# design.net
KiCad netlist of a schematic drawn in Altium Designer
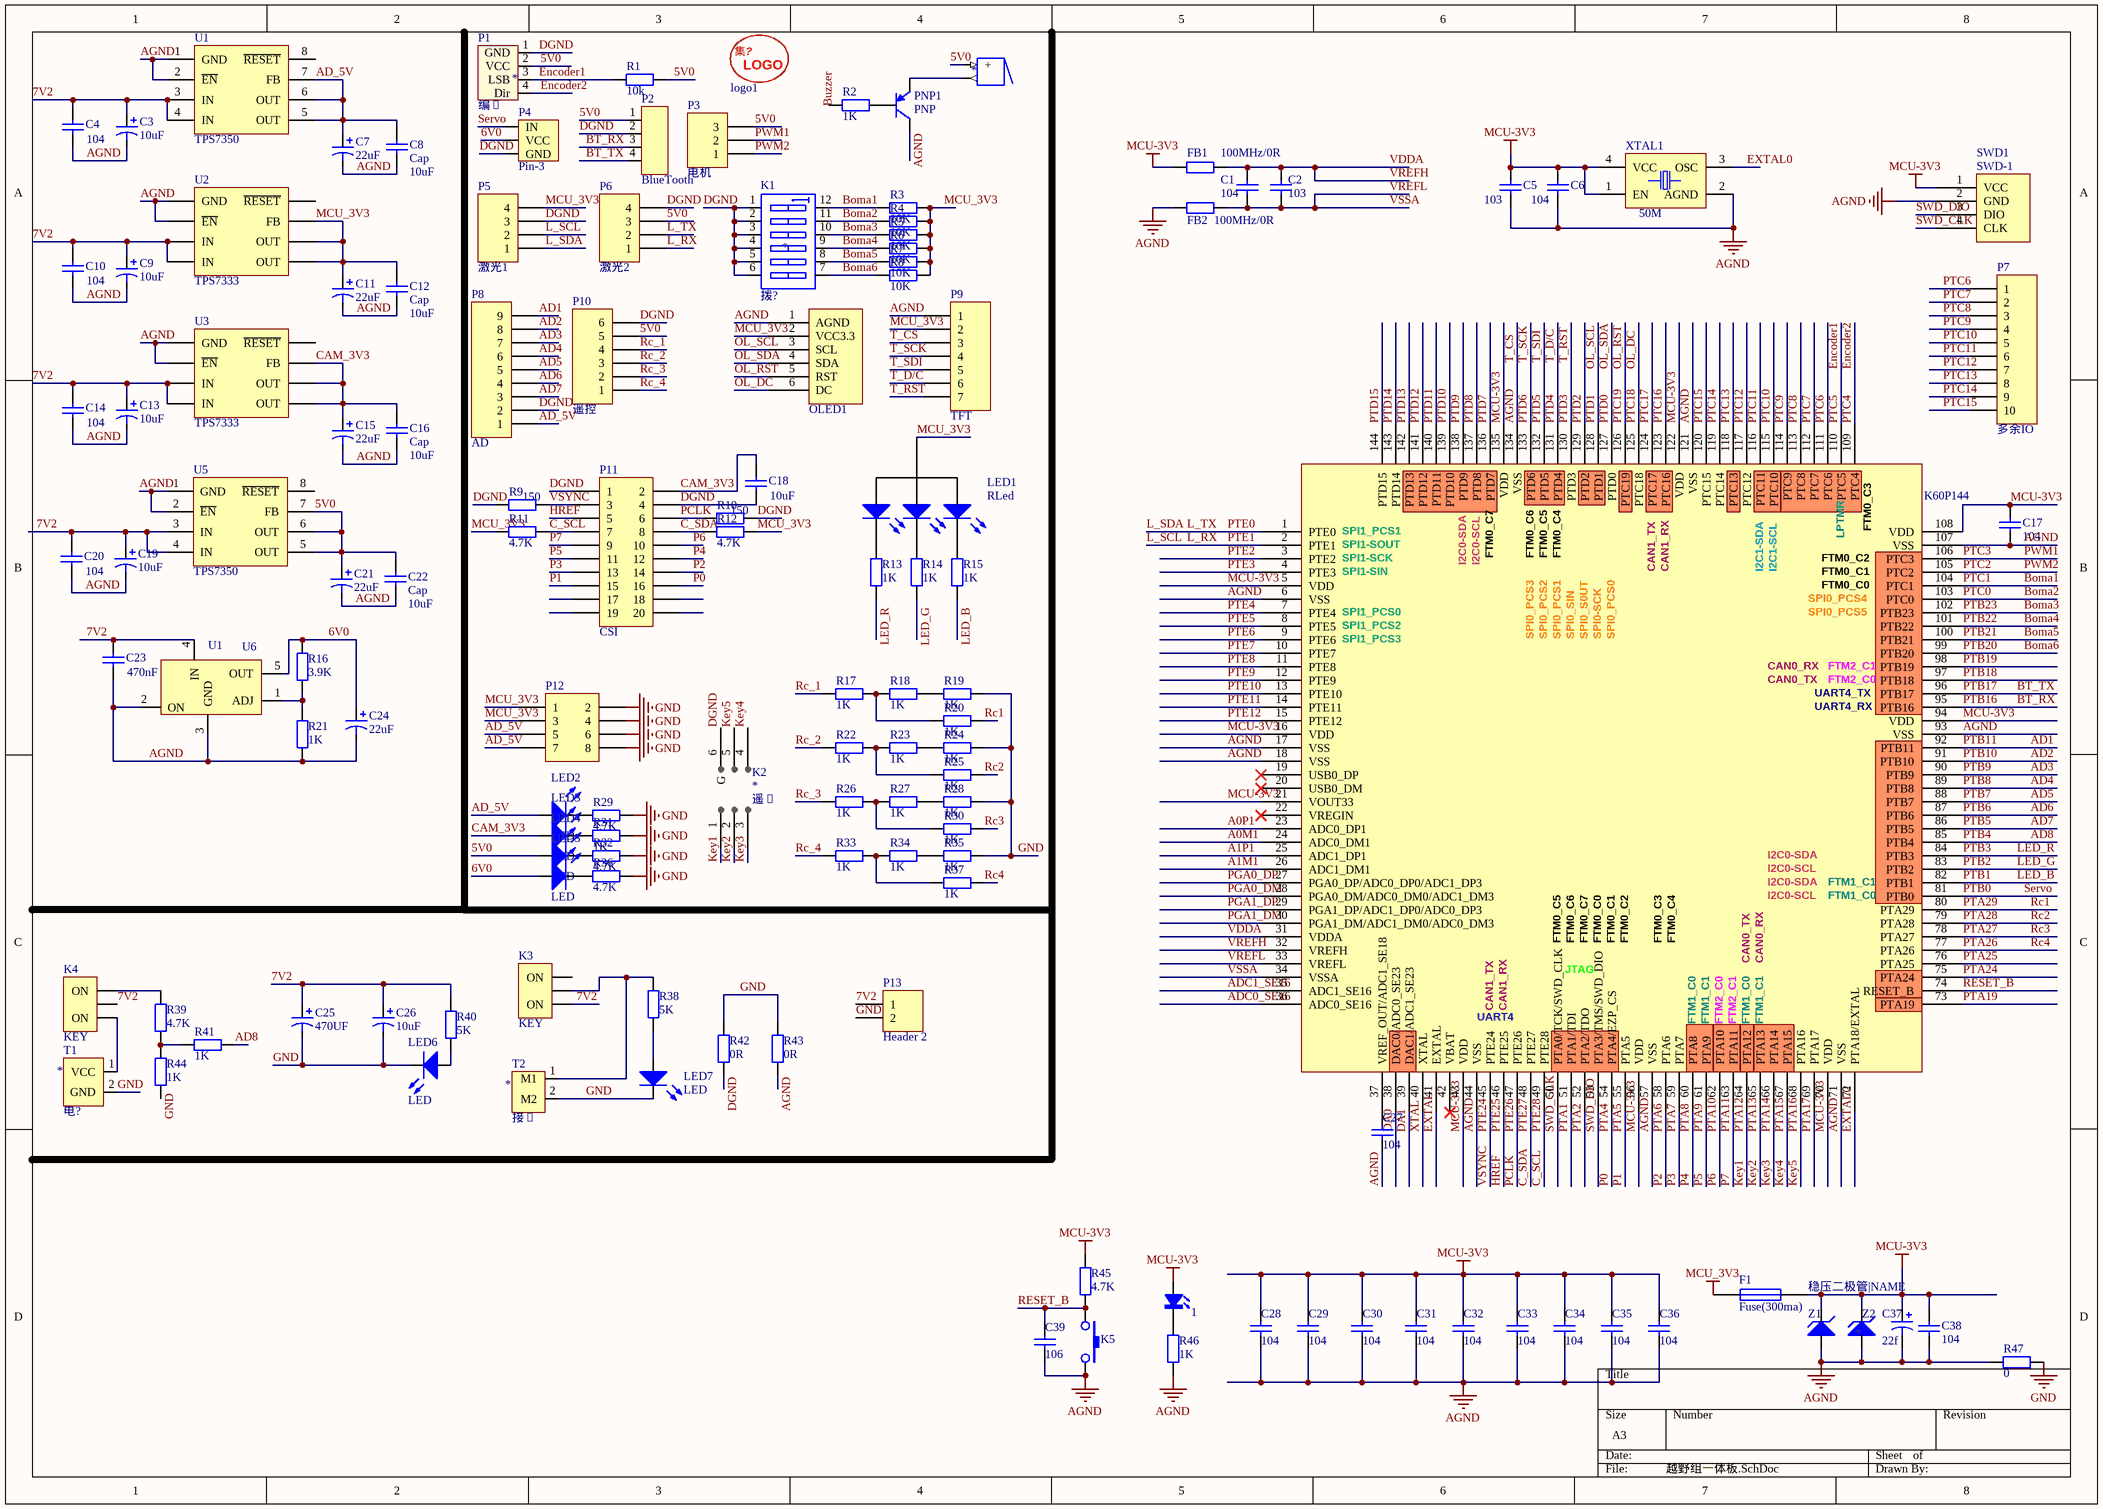
[diagram p0: 越野组一体板.SchDoc]

(export (version "E")
  (design (tool "Eeschema 10.0.6"))
  (components
    (comp (ref "1") (value "LED") (footprint "0805LED1") (libsource (lib "Bigbear") (part "LED")))
    (comp (ref "BUZZER1")
      (value "*")
      (footprint "Buzzer")
      (libsource (lib "JMU智能车专用2.0.6") (part "Buzzer(有源蜂鸣器)"))
    )
    (comp (ref "C1") (value "104") (footprint "0805-0C") (libsource (lib "K60P144") (part "CAP")))
    (comp (ref "C2") (value "103") (footprint "0805-0C") (libsource (lib "K60P144") (part "CAP")))
    (comp (ref "C3")
      (value "10uF")
      (footprint "pol cap(10uF)")
      (description "通用有极电容")
      (fields (field (name "Comment") "pol cap"))
      (libsource (lib "JMU智能车专用2.0.6") (part "pol cap"))
    )
    (comp (ref "C4")
      (value "104")
      (footprint "0805")
      (description "无极电容")
      (libsource (lib "JMU智能车专用2.0.6") (part "Cap"))
    )
    (comp (ref "C5") (value "103") (footprint "0805-0C") (libsource (lib "Bigbear") (part "CAP")))
    (comp (ref "C6") (value "104") (footprint "0805-0C") (libsource (lib "Bigbear") (part "CAP")))
    (comp (ref "C7")
      (value "22uF")
      (footprint "pol cap(10uF)")
      (description "通用有极电容")
      (fields (field (name "Comment") "pol cap"))
      (libsource (lib "JMU智能车专用2.0.6") (part "pol cap"))
    )
    (comp (ref "C8")
      (value "Cap")
      (footprint "0805")
      (description "无极电容")
      (fields (field (name "ALTIUM_VALUE") "10uF"))
      (libsource (lib "JMU智能车专用2.0.6") (part "Cap"))
    )
    (comp (ref "C9")
      (value "10uF")
      (footprint "pol cap(10uF)")
      (description "通用有极电容")
      (fields (field (name "Comment") "pol cap"))
      (libsource (lib "JMU智能车专用2.0.6") (part "pol cap"))
    )
    (comp (ref "C10")
      (value "104")
      (footprint "0805")
      (description "无极电容")
      (libsource (lib "JMU智能车专用2.0.6") (part "Cap"))
    )
    (comp (ref "C11")
      (value "22uF")
      (footprint "pol cap(10uF)")
      (description "通用有极电容")
      (fields (field (name "Comment") "pol cap"))
      (libsource (lib "JMU智能车专用2.0.6") (part "pol cap"))
    )
    (comp (ref "C12")
      (value "Cap")
      (footprint "0805")
      (description "无极电容")
      (fields (field (name "ALTIUM_VALUE") "10uF"))
      (libsource (lib "JMU智能车专用2.0.6") (part "Cap"))
    )
    (comp (ref "C13")
      (value "10uF")
      (footprint "pol cap(10uF)")
      (description "通用有极电容")
      (fields (field (name "Comment") "pol cap"))
      (libsource (lib "JMU智能车专用2.0.6") (part "pol cap"))
    )
    (comp (ref "C14")
      (value "104")
      (footprint "0805")
      (description "无极电容")
      (libsource (lib "JMU智能车专用2.0.6") (part "Cap"))
    )
    (comp (ref "C15")
      (value "22uF")
      (footprint "pol cap(10uF)")
      (description "通用有极电容")
      (fields (field (name "Comment") "pol cap"))
      (libsource (lib "JMU智能车专用2.0.6") (part "pol cap"))
    )
    (comp (ref "C16")
      (value "Cap")
      (footprint "0805")
      (description "无极电容")
      (fields (field (name "ALTIUM_VALUE") "10uF"))
      (libsource (lib "JMU智能车专用2.0.6") (part "Cap"))
    )
    (comp (ref "C17") (value "104") (footprint "0805-0C") (libsource (lib "Bigbear") (part "CAP")))
    (comp (ref "C18")
      (value "10uF")
      (footprint "0805")
      (description "无极电容")
      (libsource (lib "JMU智能车专用2.0.6") (part "Cap"))
    )
    (comp (ref "C19")
      (value "10uF")
      (footprint "pol cap(10uF)")
      (description "通用有极电容")
      (fields (field (name "Comment") "pol cap"))
      (libsource (lib "JMU智能车专用2.0.6") (part "pol cap"))
    )
    (comp (ref "C20")
      (value "104")
      (footprint "0805")
      (description "无极电容")
      (libsource (lib "JMU智能车专用2.0.6") (part "Cap"))
    )
    (comp (ref "C21")
      (value "22uF")
      (footprint "pol cap(10uF)")
      (description "通用有极电容")
      (fields (field (name "Comment") "pol cap"))
      (libsource (lib "JMU智能车专用2.0.6") (part "pol cap"))
    )
    (comp (ref "C22")
      (value "Cap")
      (footprint "0805")
      (description "无极电容")
      (fields (field (name "ALTIUM_VALUE") "10uF"))
      (libsource (lib "JMU智能车专用2.0.6") (part "Cap"))
    )
    (comp (ref "C23")
      (value "470nF")
      (footprint "0805")
      (description "无极电容")
      (libsource (lib "JMU智能车专用2.0.6") (part "Cap"))
    )
    (comp (ref "C24")
      (value "22uF")
      (footprint "pol cap(10uF)")
      (description "通用有极电容")
      (fields (field (name "Comment") "pol cap"))
      (libsource (lib "JMU智能车专用2.0.6") (part "pol cap"))
    )
    (comp (ref "C25")
      (value "470UF")
      (footprint "ED8")
      (description "ED8:470UF  ED6.3:100UF")
      (libsource (lib "JMU智能车专用2.0.6") (part "固态贴片电容"))
    )
    (comp (ref "C26")
      (value "10uF")
      (footprint "pol cap(10uF)")
      (description "通用有极电容")
      (fields (field (name "Comment") "1UF"))
      (libsource (lib "JMU智能车专用2.0.6") (part "pol cap"))
    )
    (comp (ref "C27") (value "104") (footprint "0805-0C") (libsource (lib "Bigbear") (part "CAP")))
    (comp (ref "C28") (value "104") (footprint "0805-0C") (libsource (lib "Bigbear") (part "CAP")))
    (comp (ref "C29") (value "104") (footprint "0805-0C") (libsource (lib "Bigbear") (part "CAP")))
    (comp (ref "C30") (value "104") (footprint "0805-0C") (libsource (lib "Bigbear") (part "CAP")))
    (comp (ref "C31") (value "104") (footprint "0805-0C") (libsource (lib "Bigbear") (part "CAP")))
    (comp (ref "C32") (value "104") (footprint "0805-0C") (libsource (lib "Bigbear") (part "CAP")))
    (comp (ref "C33") (value "104") (footprint "0805-0C") (libsource (lib "Bigbear") (part "CAP")))
    (comp (ref "C34") (value "104") (footprint "0805-0C") (libsource (lib "Bigbear") (part "CAP")))
    (comp (ref "C35") (value "104") (footprint "0805-0C") (libsource (lib "Bigbear") (part "CAP")))
    (comp (ref "C36") (value "104") (footprint "0805-0C") (libsource (lib "Bigbear") (part "CAP")))
    (comp (ref "C37") (value "22f") (footprint "3528-B-TA") (libsource (lib "Bigbear") (part "CAP-TAN")))
    (comp (ref "C38") (value "104") (footprint "0805-0C") (libsource (lib "Bigbear") (part "CAP")))
    (comp (ref "C39") (value "106") (footprint "0805-0C") (libsource (lib "Bigbear") (part "CAP")))
    (comp (ref "F1")
      (value "Fuse(300ma)")
      (footprint "1206R")
      (description "Fuse")
      (libsource (lib "Bigbear") (part "Fuse"))
    )
    (comp (ref "FB1") (value "100MHz/0R") (footprint "0805") (libsource (lib "K60P144") (part "RES")))
    (comp (ref "FB2") (value "100MHz/0R") (footprint "0805") (libsource (lib "K60P144") (part "RES")))
    (comp (ref "K1")
      (value "*")
      (footprint "拨码开关*6")
      (fields (field (name "ALTIUM_UNNAMED_2") "拨?"))
      (libsource (lib "JMU智能车专用2.0.6") (part "拨码开关（6位）"))
    )
    (comp (ref "K2")
      (value "*")
      (footprint "摇杆开关")
      (fields (field (name "ALTIUM_UNNAMED_1") "Ò£¸"))
      (libsource (lib "彬源的集成库") (part "遥感开关"))
    )
    (comp (ref "K3")
      (value "KEY")
      (footprint "钮子开关（大）")
      (description "AC 250V/6A")
      (libsource (lib "JMU智能车专用2.0.6") (part "钮子开关（大）"))
    )
    (comp (ref "K4")
      (value "KEY")
      (footprint "钮子开关（大）")
      (description "AC 250V/6A")
      (libsource (lib "JMU智能车专用2.0.6") (part "钮子开关（大）"))
    )
    (comp (ref "K5")
      (value "RESET")
      (footprint "SW_PB2_A1")
      (description "按键")
      (libsource (lib "Bigbear") (part "KEY"))
    )
    (comp (ref "LED1") (value "RLed") (footprint "Rled") (libsource (lib "DR") (part "RLed")))
    (comp (ref "LED2")
      (value "LED")
      (footprint "LED(0805)")
      (description "发光二极管")
      (libsource (lib "JMU智能车专用2.0.6") (part "LED"))
    )
    (comp (ref "LED3")
      (value "LED")
      (footprint "LED(0805)")
      (description "发光二极管")
      (libsource (lib "JMU智能车专用2.0.6") (part "LED"))
    )
    (comp (ref "LED4")
      (value "LED")
      (footprint "LED(0805)")
      (description "发光二极管")
      (libsource (lib "JMU智能车专用2.0.6") (part "LED"))
    )
    (comp (ref "LED5")
      (value "LED")
      (footprint "LED(0805)")
      (description "发光二极管")
      (libsource (lib "JMU智能车专用2.0.6") (part "LED"))
    )
    (comp (ref "LED6")
      (value "LED")
      (footprint "LED(0805)")
      (description "发光二极管")
      (libsource (lib "JMU智能车专用2.0.6") (part "LED"))
    )
    (comp (ref "LED7")
      (value "LED")
      (footprint "LED(0805)")
      (description "发光二极管")
      (libsource (lib "JMU智能车专用2.0.6") (part "LED"))
    )
    (comp (ref "logo1")
      (value "LOGO(JMU)")
      (footprint "JMU_logo（1）")
      (libsource (lib "JMU智能车专用2.0.6") (part "JMU-LOGO"))
    )
    (comp (ref "OLED1") (value "OLED") (footprint "S0P6") (libsource (lib "Bigbear") (part "OLED")))
    (comp (ref "P1")
      (value "*")
      (footprint "编码器")
      (fields (field (name "ALTIUM_UNNAMED_2") "±àÂ"))
      (libsource (lib "JMU智能车专用2.0.6") (part "编码器"))
    )
    (comp (ref "P2") (value "BlueTooth") (footprint "插针——4") (libsource (lib "彬源的集成库") (part "插针——4")))
    (comp (ref "P3")
      (value "电机")
      (footprint "HDR1X3")
      (description "Header, 3-Pin")
      (fields (field (name "PUBLISHER") "Altium Limited"))
      (libsource (lib "Miscellaneous Connectors") (part "Header 3"))
    )
    (comp (ref "P4")
      (value "Pin-3")
      (footprint "HDR_1X3")
      (description "舵机...")
      (libsource (lib "JMU智能车专用2.0.6") (part "舵机"))
    )
    (comp (ref "P5")
      (value "激光1")
      (footprint "HDR1X4")
      (description "Header, 4-Pin")
      (fields (field (name "PUBLISHER") "Altium Limited"))
      (libsource (lib "Miscellaneous Connectors") (part "Header 4"))
    )
    (comp (ref "P6")
      (value "激光2")
      (footprint "HDR1X4")
      (description "Header, 4-Pin")
      (fields (field (name "PUBLISHER") "Altium Limited"))
      (libsource (lib "Miscellaneous Connectors") (part "Header 4"))
    )
    (comp (ref "P7")
      (value "多余IO")
      (footprint "HDR1X10")
      (description "Header, 10-Pin")
      (fields (field (name "PUBLISHER") "Altium Limited"))
      (libsource (lib "Miscellaneous Connectors") (part "Header 10"))
    )
    (comp (ref "P8")
      (value "AD")
      (footprint "HDR1X9")
      (description "Header, 9-Pin")
      (fields (field (name "PUBLISHER") "Altium Limited"))
      (libsource (lib "Miscellaneous Connectors") (part "Header 9"))
    )
    (comp (ref "P9")
      (value "TFT")
      (footprint "HDR1X7")
      (description "Header, 7-Pin")
      (fields (field (name "PUBLISHER") "Altium Limited"))
      (libsource (lib "Miscellaneous Connectors") (part "Header 7"))
    )
    (comp (ref "P10")
      (value "遥控")
      (footprint "HDR1X6")
      (description "Header, 6-Pin")
      (fields (field (name "PUBLISHER") "Altium Limited"))
      (libsource (lib "Miscellaneous Connectors") (part "Header 6"))
    )
    (comp (ref "P11")
      (value "CSI")
      (footprint "HDR2X10")
      (description "Header, 10-Pin, Dual row")
      (fields (field (name "PUBLISHER") "Altium Limited"))
      (libsource (lib "Miscellaneous Connectors") (part "Header 10X2"))
    )
    (comp (ref "P12")
      (value "Header 4X2")
      (footprint "HDR2X4")
      (description "Header, 4-Pin, Dual row")
      (fields (field (name "PUBLISHER") "Altium Limited"))
      (libsource (lib "Miscellaneous Connectors") (part "Header 4X2"))
    )
    (comp (ref "P13")
      (value "Header 2")
      (footprint "HDR1X2")
      (description "Header, 2-Pin")
      (fields (field (name "PUBLISHER") "Altium Limited"))
      (libsource (lib "Miscellaneous Connectors") (part "Header 2"))
    )
    (comp (ref "PNP1") (value "PNP") (footprint "PNP") (libsource (lib "JMU智能车专用2.0.6") (part "PNP")))
    (comp (ref "R1")
      (value "10k")
      (footprint "0805")
      (description "通用电阻")
      (libsource (lib "JMU智能车专用2.0.6") (part "Res"))
    )
    (comp (ref "R2") (value "1K") (footprint "0805") (description "通用电阻") (libsource (lib "") (part "Res_1")))
    (comp (ref "R3")
      (value "10K")
      (footprint "0805")
      (description "通用电阻")
      (libsource (lib "") (part "Res_1"))
    )
    (comp (ref "R4")
      (value "10K")
      (footprint "0805")
      (description "通用电阻")
      (libsource (lib "") (part "Res_1"))
    )
    (comp (ref "R5")
      (value "10K")
      (footprint "0805")
      (description "通用电阻")
      (libsource (lib "") (part "Res_1"))
    )
    (comp (ref "R6")
      (value "10K")
      (footprint "0805")
      (description "通用电阻")
      (libsource (lib "") (part "Res_1"))
    )
    (comp (ref "R7")
      (value "10K")
      (footprint "0805")
      (description "通用电阻")
      (libsource (lib "") (part "Res_1"))
    )
    (comp (ref "R8")
      (value "10K")
      (footprint "0805")
      (description "通用电阻")
      (libsource (lib "") (part "Res_1"))
    )
    (comp (ref "R9")
      (value "150")
      (footprint "0805")
      (description "通用电阻")
      (libsource (lib "JMU智能车专用2.0.6") (part "Res"))
    )
    (comp (ref "R10")
      (value "150")
      (footprint "0805")
      (description "通用电阻")
      (libsource (lib "JMU智能车专用2.0.6") (part "Res"))
    )
    (comp (ref "R11")
      (value "4.7K")
      (footprint "0805")
      (description "通用电阻")
      (libsource (lib "JMU智能车专用3.0.6") (part "Res"))
    )
    (comp (ref "R12")
      (value "4.7K")
      (footprint "0805")
      (description "通用电阻")
      (libsource (lib "JMU智能车专用3.0.6") (part "Res"))
    )
    (comp (ref "R13")
      (value "1K")
      (footprint "0805")
      (description "通用电阻")
      (libsource (lib "") (part "Res_1"))
    )
    (comp (ref "R14")
      (value "1K")
      (footprint "0805")
      (description "通用电阻")
      (libsource (lib "") (part "Res_1"))
    )
    (comp (ref "R15")
      (value "1K")
      (footprint "0805")
      (description "通用电阻")
      (libsource (lib "") (part "Res_1"))
    )
    (comp (ref "R16")
      (value "3.9K")
      (footprint "0805")
      (description "通用电阻")
      (libsource (lib "") (part "Res_2"))
    )
    (comp (ref "R17")
      (value "1K")
      (footprint "0805")
      (description "通用电阻")
      (libsource (lib "JMU智能车专用3.0.6") (part "Res"))
    )
    (comp (ref "R18")
      (value "1K")
      (footprint "0805")
      (description "通用电阻")
      (libsource (lib "JMU智能车专用3.0.6") (part "Res"))
    )
    (comp (ref "R19")
      (value "1K")
      (footprint "0805")
      (description "通用电阻")
      (libsource (lib "JMU智能车专用3.0.6") (part "Res"))
    )
    (comp (ref "R20")
      (value "1K")
      (footprint "0805")
      (description "通用电阻")
      (libsource (lib "JMU智能车专用3.0.6") (part "Res"))
    )
    (comp (ref "R21")
      (value "1K")
      (footprint "0805")
      (description "通用电阻")
      (libsource (lib "") (part "Res_2"))
    )
    (comp (ref "R22")
      (value "1K")
      (footprint "0805")
      (description "通用电阻")
      (libsource (lib "JMU智能车专用3.0.6") (part "Res"))
    )
    (comp (ref "R23")
      (value "1K")
      (footprint "0805")
      (description "通用电阻")
      (libsource (lib "JMU智能车专用3.0.6") (part "Res"))
    )
    (comp (ref "R24")
      (value "1K")
      (footprint "0805")
      (description "通用电阻")
      (libsource (lib "JMU智能车专用3.0.6") (part "Res"))
    )
    (comp (ref "R25")
      (value "1K")
      (footprint "0805")
      (description "通用电阻")
      (libsource (lib "JMU智能车专用3.0.6") (part "Res"))
    )
    (comp (ref "R26")
      (value "1K")
      (footprint "0805")
      (description "通用电阻")
      (libsource (lib "JMU智能车专用3.0.6") (part "Res"))
    )
    (comp (ref "R27")
      (value "1K")
      (footprint "0805")
      (description "通用电阻")
      (libsource (lib "JMU智能车专用3.0.6") (part "Res"))
    )
    (comp (ref "R28")
      (value "1K")
      (footprint "0805")
      (description "通用电阻")
      (libsource (lib "JMU智能车专用3.0.6") (part "Res"))
    )
    (comp (ref "R29")
      (value "4.7K")
      (footprint "0805")
      (description "通用电阻")
      (libsource (lib "JMU智能车专用3.0.6") (part "Res"))
    )
    (comp (ref "R30")
      (value "1K")
      (footprint "0805")
      (description "通用电阻")
      (libsource (lib "JMU智能车专用3.0.6") (part "Res"))
    )
    (comp (ref "R31")
      (value "1K")
      (footprint "0805")
      (description "通用电阻")
      (libsource (lib "JMU智能车专用3.0.6") (part "Res"))
    )
    (comp (ref "R32")
      (value "4.7K")
      (footprint "0805")
      (description "通用电阻")
      (libsource (lib "JMU智能车专用3.0.6") (part "Res"))
    )
    (comp (ref "R33")
      (value "1K")
      (footprint "0805")
      (description "通用电阻")
      (libsource (lib "JMU智能车专用3.0.6") (part "Res"))
    )
    (comp (ref "R34")
      (value "1K")
      (footprint "0805")
      (description "通用电阻")
      (libsource (lib "JMU智能车专用3.0.6") (part "Res"))
    )
    (comp (ref "R35")
      (value "1K")
      (footprint "0805")
      (description "通用电阻")
      (libsource (lib "JMU智能车专用3.0.6") (part "Res"))
    )
    (comp (ref "R36")
      (value "4.7K")
      (footprint "0805")
      (description "通用电阻")
      (libsource (lib "JMU智能车专用3.0.6") (part "Res"))
    )
    (comp (ref "R37")
      (value "1K")
      (footprint "0805")
      (description "通用电阻")
      (libsource (lib "JMU智能车专用3.0.6") (part "Res"))
    )
    (comp (ref "R38")
      (value "5K")
      (footprint "0805")
      (description "通用电阻")
      (libsource (lib "") (part "Res_2"))
    )
    (comp (ref "R39")
      (value "4.7K")
      (footprint "0805")
      (description "通用电阻")
      (libsource (lib "") (part "Res_1"))
    )
    (comp (ref "R40")
      (value "5K")
      (footprint "0805")
      (description "通用电阻")
      (libsource (lib "") (part "Res_2"))
    )
    (comp (ref "R41")
      (value "1K")
      (footprint "0805")
      (description "通用电阻")
      (libsource (lib "") (part "Res_2"))
    )
    (comp (ref "R42")
      (value "0R")
      (footprint "0805")
      (description "通用电阻")
      (libsource (lib "") (part "Res_3"))
    )
    (comp (ref "R43")
      (value "0R")
      (footprint "0805")
      (description "通用电阻")
      (libsource (lib "") (part "Res_3"))
    )
    (comp (ref "R44")
      (value "1K")
      (footprint "0805")
      (description "通用电阻")
      (libsource (lib "") (part "Res_1"))
    )
    (comp (ref "R45") (value "4.7K") (footprint "0603-r") (libsource (lib "Bigbear") (part "RES")))
    (comp (ref "R46") (value "1K") (footprint "0603-r") (libsource (lib "Bigbear") (part "RES")))
    (comp (ref "R47") (value "0") (footprint "0603-r") (libsource (lib "") (part "RES_1")))
    (comp (ref "SWD1") (value "SWD-1") (libsource (lib "K60P144") (part "SWD-1")))
    (comp (ref "T1")
      (value "*")
      (footprint "T型接头")
      (description "电源线")
      (fields (field (name "ALTIUM_UNNAMED_2") "电?"))
      (libsource (lib "JMU智能车专用2.0.7") (part "电源接线端子"))
    )
    (comp (ref "T2")
      (value "*")
      (footprint "接线端子")
      (fields (field (name "ALTIUM_UNNAMED_3") "½ÓÏ"))
      (libsource (lib "JMU智能车专用2.0.6") (part "接线端子"))
    )
    (comp (ref "U1")
      (value "TPS7350")
      (footprint "SOIC-8")
      (description "稳压元件（5V）")
      (libsource (lib "JMU智能车专用2.0.7") (part "TPS7350"))
    )
    (comp (ref "U2")
      (value "TPS7333")
      (footprint "SOIC-8")
      (description "稳压元件（3.3V）")
      (libsource (lib "JMU智能车专用2.0.6") (part "TPS7333"))
    )
    (comp (ref "U3")
      (value "TPS7333")
      (footprint "SOIC-8")
      (description "稳压元件（3.3V）")
      (libsource (lib "JMU智能车专用2.0.6") (part "TPS7333"))
    )
    (comp (ref "U4") (value "K60P144") (footprint "LQFP144") (libsource (lib "Bigbear") (part "K60P144")))
    (comp (ref "U5")
      (value "TPS7350")
      (footprint "SOIC-8")
      (description "稳压元件（5V）")
      (libsource (lib "JMU智能车专用2.0.7") (part "TPS7350"))
    )
    (comp (ref "U6")
      (value "U1")
      (footprint "LM2941")
      (description "稳压元件-->6V")
      (libsource (lib "JMU智能车专用2.0.6") (part "LM2941"))
    )
    (comp (ref "XTAL1") (value "50M") (footprint "XTAL-3225") (libsource (lib "Bigbear") (part "XTAL")))
    (comp (ref "Z1") (value "Zener") (footprint "0805-0C") (libsource (lib "Bigbear") (part "Zener")))
    (comp (ref "Z2")
      (value "*")
      (footprint "0805-0C")
      (fields (field (name "ALTIUM_UNNAMED_1") "稳压二极管"))
      (libsource (lib "Bigbear") (part "Zener"))
    )
  )
  (nets
    (net (code "1") (name "/5V0") (class "Default")
      (node (ref "BUZZER1") (pin "1") (pinfunction "+_1") (pintype "input"))
      (node (ref "C21") (pin "1") (pinfunction "1_1") (pintype "passive"))
      (node (ref "C22") (pin "2") (pinfunction "2_2") (pintype "passive"))
      (node (ref "LED4") (pin "1") (pinfunction "A_1") (pintype "passive"))
      (node (ref "P1") (pin "2") (pinfunction "VCC_2") (pintype "power_in"))
      (node (ref "P10") (pin "5") (pinfunction "5_5") (pintype "passive"))
      (node (ref "P2") (pin "1") (pintype "passive"))
      (node (ref "P3") (pin "3") (pinfunction "3_3") (pintype "passive"))
      (node (ref "P6") (pin "3") (pinfunction "3_3") (pintype "passive"))
      (node (ref "R1") (pin "2") (pinfunction "2_2") (pintype "passive"))
      (node (ref "U5") (pin "5") (pinfunction "OUT_5") (pintype "power_in"))
      (node (ref "U5") (pin "6") (pinfunction "OUT_6") (pintype "power_in"))
      (node (ref "U5") (pin "7") (pinfunction "FB_7") (pintype "power_in"))
    )
    (net (code "2") (name "/6V0") (class "Default")
      (node (ref "C24") (pin "1") (pinfunction "1_1") (pintype "passive"))
      (node (ref "LED5") (pin "1") (pinfunction "A_1") (pintype "passive"))
      (node (ref "P4") (pin "2") (pinfunction "VCC_2") (pintype "passive"))
      (node (ref "R16") (pin "2") (pinfunction "2_2") (pintype "passive"))
      (node (ref "U6") (pin "5") (pinfunction "OUT_5") (pintype "passive"))
    )
    (net (code "3") (name "/7V2") (class "Default")
      (node (ref "C10") (pin "2") (pinfunction "2_2") (pintype "passive"))
      (node (ref "C13") (pin "1") (pinfunction "1_1") (pintype "passive"))
      (node (ref "C14") (pin "2") (pinfunction "2_2") (pintype "passive"))
      (node (ref "C19") (pin "1") (pinfunction "1_1") (pintype "passive"))
      (node (ref "C20") (pin "2") (pinfunction "2_2") (pintype "passive"))
      (node (ref "C23") (pin "2") (pinfunction "2_2") (pintype "passive"))
      (node (ref "C25") (pin "1") (pinfunction "1_1") (pintype "passive"))
      (node (ref "C26") (pin "1") (pinfunction "1_1") (pintype "passive"))
      (node (ref "C3") (pin "1") (pinfunction "1_1") (pintype "passive"))
      (node (ref "C4") (pin "2") (pinfunction "2_2") (pintype "passive"))
      (node (ref "C9") (pin "1") (pinfunction "1_1") (pintype "passive"))
      (node (ref "K3") (pin "1") (pinfunction "ON_1") (pintype "passive"))
      (node (ref "K4") (pin "2") (pinfunction "com_2") (pintype "passive"))
      (node (ref "P13") (pin "1") (pinfunction "1_1") (pintype "passive"))
      (node (ref "R40") (pin "2") (pinfunction "2_2") (pintype "passive"))
      (node (ref "U1") (pin "3") (pinfunction "IN_3") (pintype "power_in"))
      (node (ref "U1") (pin "4") (pinfunction "IN_4") (pintype "power_in"))
      (node (ref "U2") (pin "3") (pinfunction "IN_3") (pintype "power_in"))
      (node (ref "U2") (pin "4") (pinfunction "IN_4") (pintype "power_in"))
      (node (ref "U3") (pin "3") (pinfunction "IN_3") (pintype "power_in"))
      (node (ref "U3") (pin "4") (pinfunction "IN_4") (pintype "power_in"))
      (node (ref "U5") (pin "3") (pinfunction "IN_3") (pintype "power_in"))
      (node (ref "U5") (pin "4") (pinfunction "IN_4") (pintype "power_in"))
      (node (ref "U6") (pin "4") (pinfunction "IN_4") (pintype "passive"))
    )
    (net (code "4") (name "/A0M1") (class "Default")
      (node (ref "U4") (pin "24") (pinfunction "ADC0_DM1_24") (pintype "passive"))
    )
    (net (code "5") (name "/A0P1") (class "Default")
      (node (ref "U4") (pin "23") (pinfunction "ADC0_DP1_23") (pintype "passive"))
    )
    (net (code "6") (name "/A1M1") (class "Default")
      (node (ref "U4") (pin "26") (pinfunction "ADC1_DM1_26") (pintype "passive"))
    )
    (net (code "7") (name "/A1P1") (class "Default")
      (node (ref "U4") (pin "25") (pinfunction "ADC1_DP1_25") (pintype "passive"))
    )
    (net (code "8") (name "/AD1") (class "Default")
      (node (ref "P8") (pin "9") (pinfunction "9_9") (pintype "passive"))
      (node (ref "U4") (pin "92") (pinfunction "PTB11_92") (pintype "passive"))
    )
    (net (code "9") (name "/AD2") (class "Default")
      (node (ref "P8") (pin "8") (pinfunction "8_8") (pintype "passive"))
      (node (ref "U4") (pin "91") (pinfunction "PTB10_91") (pintype "passive"))
    )
    (net (code "10") (name "/AD3") (class "Default")
      (node (ref "P8") (pin "7") (pinfunction "7_7") (pintype "passive"))
      (node (ref "U4") (pin "90") (pinfunction "PTB9_90") (pintype "passive"))
    )
    (net (code "11") (name "/AD4") (class "Default")
      (node (ref "P8") (pin "6") (pinfunction "6_6") (pintype "passive"))
      (node (ref "U4") (pin "89") (pinfunction "PTB8_89") (pintype "passive"))
    )
    (net (code "12") (name "/AD5") (class "Default")
      (node (ref "P8") (pin "5") (pinfunction "5_5") (pintype "passive"))
      (node (ref "U4") (pin "88") (pinfunction "PTB7_88") (pintype "passive"))
    )
    (net (code "13") (name "/AD6") (class "Default")
      (node (ref "P8") (pin "4") (pinfunction "4_4") (pintype "passive"))
      (node (ref "U4") (pin "87") (pinfunction "PTB6_87") (pintype "passive"))
    )
    (net (code "14") (name "/AD7") (class "Default")
      (node (ref "P8") (pin "3") (pinfunction "3_3") (pintype "passive"))
      (node (ref "U4") (pin "86") (pinfunction "PTB5_86") (pintype "passive"))
    )
    (net (code "15") (name "/AD8") (class "Default")
      (node (ref "R41") (pin "1") (pinfunction "1_1") (pintype "passive"))
      (node (ref "U4") (pin "85") (pinfunction "PTB4_85") (pintype "passive"))
    )
    (net (code "16") (name "/ADC0_SE16") (class "Default")
      (node (ref "U4") (pin "36") (pinfunction "ADC0_SE16_36") (pintype "passive"))
    )
    (net (code "17") (name "/ADC1_SE16") (class "Default")
      (node (ref "U4") (pin "35") (pinfunction "ADC1_SE16_35") (pintype "passive"))
    )
    (net (code "18") (name "/AD_5V") (class "Default")
      (node (ref "C7") (pin "1") (pinfunction "1_1") (pintype "passive"))
      (node (ref "C8") (pin "2") (pinfunction "2_2") (pintype "passive"))
      (node (ref "LED2") (pin "1") (pinfunction "A_1") (pintype "passive"))
      (node (ref "P12") (pin "5") (pinfunction "5_5") (pintype "passive"))
      (node (ref "P12") (pin "7") (pinfunction "7_7") (pintype "passive"))
      (node (ref "P8") (pin "1") (pinfunction "1_1") (pintype "passive"))
      (node (ref "U1") (pin "5") (pinfunction "OUT_5") (pintype "power_in"))
      (node (ref "U1") (pin "6") (pinfunction "OUT_6") (pintype "power_in"))
      (node (ref "U1") (pin "7") (pinfunction "FB_7") (pintype "power_in"))
    )
    (net (code "19") (name "/BT_RX") (class "Default")
      (node (ref "P2") (pin "3") (pintype "passive"))
      (node (ref "U4") (pin "95") (pinfunction "PTB16_95") (pintype "passive"))
    )
    (net (code "20") (name "/BT_TX") (class "Default")
      (node (ref "P2") (pin "4") (pintype "passive"))
      (node (ref "U4") (pin "96") (pinfunction "PTB17_96") (pintype "passive"))
    )
    (net (code "21") (name "/Boma1") (class "Default")
      (node (ref "K1") (pin "12") (pinfunction "B1_12") (pintype "passive"))
      (node (ref "R3") (pin "2") (pinfunction "2_2") (pintype "passive"))
      (node (ref "U4") (pin "104") (pinfunction "PTC1_104") (pintype "passive"))
    )
    (net (code "22") (name "/Boma2") (class "Default")
      (node (ref "K1") (pin "11") (pinfunction "B2_11") (pintype "passive"))
      (node (ref "R4") (pin "2") (pinfunction "2_2") (pintype "passive"))
      (node (ref "U4") (pin "103") (pinfunction "PTC0_103") (pintype "passive"))
    )
    (net (code "23") (name "/Boma3") (class "Default")
      (node (ref "K1") (pin "10") (pinfunction "B3_10") (pintype "passive"))
      (node (ref "R5") (pin "2") (pinfunction "2_2") (pintype "passive"))
      (node (ref "U4") (pin "102") (pinfunction "PTB23_102") (pintype "passive"))
    )
    (net (code "24") (name "/Boma4") (class "Default")
      (node (ref "K1") (pin "9") (pinfunction "B4_9") (pintype "passive"))
      (node (ref "R6") (pin "2") (pinfunction "2_2") (pintype "passive"))
      (node (ref "U4") (pin "101") (pinfunction "PTB22_101") (pintype "passive"))
    )
    (net (code "25") (name "/Boma5") (class "Default")
      (node (ref "K1") (pin "8") (pinfunction "B5_8") (pintype "passive"))
      (node (ref "R7") (pin "2") (pinfunction "2_2") (pintype "passive"))
      (node (ref "U4") (pin "100") (pinfunction "PTB21_100") (pintype "passive"))
    )
    (net (code "26") (name "/Boma6") (class "Default")
      (node (ref "K1") (pin "7") (pinfunction "B5_7") (pintype "passive"))
      (node (ref "R8") (pin "2") (pinfunction "2_2") (pintype "passive"))
      (node (ref "U4") (pin "99") (pinfunction "PTB20_99") (pintype "passive"))
    )
    (net (code "28") (name "/CAM_3V3") (class "Default")
      (node (ref "C15") (pin "1") (pinfunction "1_1") (pintype "passive"))
      (node (ref "C16") (pin "2") (pinfunction "2_2") (pintype "passive"))
      (node (ref "C18") (pin "2") (pinfunction "2_2") (pintype "passive"))
      (node (ref "LED3") (pin "1") (pinfunction "A_1") (pintype "passive"))
      (node (ref "P11") (pin "2") (pinfunction "2_2") (pintype "passive"))
      (node (ref "U3") (pin "5") (pinfunction "OUT_5") (pintype "power_in"))
      (node (ref "U3") (pin "6") (pinfunction "OUT_6") (pintype "power_in"))
      (node (ref "U3") (pin "7") (pinfunction "FB_7") (pintype "power_in"))
    )
    (net (code "29") (name "/C_SCL") (class "Default")
      (node (ref "P11") (pin "7") (pinfunction "7_7") (pintype "passive"))
      (node (ref "R11") (pin "2") (pinfunction "2_2") (pintype "passive"))
      (node (ref "U4") (pin "49") (pinfunction "PTE28_49") (pintype "passive"))
    )
    (net (code "30") (name "/C_SDA") (class "Default")
      (node (ref "P11") (pin "8") (pinfunction "8_8") (pintype "passive"))
      (node (ref "R12") (pin "1") (pinfunction "1_1") (pintype "passive"))
      (node (ref "U4") (pin "48") (pinfunction "PTE27_48") (pintype "passive"))
    )
    (net (code "31") (name "/DA0") (class "Default")
      (node (ref "U4") (pin "38") (pinfunction "DAC0/ADC0_SE23_38") (pintype "passive"))
    )
    (net (code "32") (name "/DA1") (class "Default")
      (node (ref "U4") (pin "39") (pinfunction "DAC1/ADC1_SE23_39") (pintype "passive"))
    )
    (net (code "33") (name "/DGND") (class "Default")
      (node (ref "C18") (pin "1") (pinfunction "1_1") (pintype "passive"))
      (node (ref "K1") (pin "1") (pinfunction "A1_1") (pintype "passive"))
      (node (ref "K1") (pin "2") (pinfunction "A2_2") (pintype "passive"))
      (node (ref "K1") (pin "3") (pinfunction "A3_3") (pintype "passive"))
      (node (ref "K1") (pin "4") (pinfunction "A4_4") (pintype "passive"))
      (node (ref "K1") (pin "5") (pinfunction "A5_5") (pintype "passive"))
      (node (ref "K1") (pin "6") (pinfunction "A5_6") (pintype "passive"))
      (node (ref "K2") (pin "6") (pinfunction "G_6") (pintype "passive"))
      (node (ref "P1") (pin "1") (pinfunction "GND_1") (pintype "power_in"))
      (node (ref "P10") (pin "6") (pinfunction "6_6") (pintype "passive"))
      (node (ref "P11") (pin "1") (pinfunction "1_1") (pintype "passive"))
      (node (ref "P11") (pin "4") (pinfunction "4_4") (pintype "passive"))
      (node (ref "P2") (pin "2") (pintype "passive"))
      (node (ref "P4") (pin "3") (pinfunction "GND_3") (pintype "passive"))
      (node (ref "P5") (pin "3") (pinfunction "3_3") (pintype "passive"))
      (node (ref "P6") (pin "4") (pinfunction "4_4") (pintype "passive"))
      (node (ref "P8") (pin "2") (pinfunction "2_2") (pintype "passive"))
      (node (ref "R10") (pin "2") (pinfunction "2_2") (pintype "passive"))
      (node (ref "R42") (pin "2") (pinfunction "2_2") (pintype "passive"))
      (node (ref "R9") (pin "1") (pinfunction "1_1") (pintype "passive"))
    )
    (net (code "34") (name "/EXTAL") (class "Default")
      (node (ref "U4") (pin "41") (pinfunction "EXTAL_41") (pintype "passive"))
    )
    (net (code "35") (name "/EXTAL0") (class "Default")
      (node (ref "U4") (pin "72") (pinfunction "PTA18/EXTAL_72") (pintype "passive"))
      (node (ref "XTAL1") (pin "3") (pinfunction "OSC_3") (pintype "passive"))
    )
    (net (code "36") (name "/Encoder1") (class "Default")
      (node (ref "P1") (pin "3") (pinfunction "LSB_3") (pintype "power_in"))
      (node (ref "R1") (pin "1") (pinfunction "1_1") (pintype "passive"))
      (node (ref "U4") (pin "110") (pinfunction "PTC5_110") (pintype "passive"))
    )
    (net (code "37") (name "/Encoder2") (class "Default")
      (node (ref "P1") (pin "4") (pinfunction "Dir_4") (pintype "power_in"))
      (node (ref "U4") (pin "109") (pinfunction "PTC4_109") (pintype "passive"))
    )
    (net (code "38") (name "/HREF") (class "Default")
      (node (ref "P11") (pin "5") (pinfunction "5_5") (pintype "passive"))
      (node (ref "U4") (pin "46") (pinfunction "PTE25_46") (pintype "passive"))
    )
    (net (code "39") (name "/Key1") (class "Default")
      (node (ref "K2") (pin "1") (pintype "passive"))
      (node (ref "U4") (pin "64") (pinfunction "PTA12_64") (pintype "passive"))
    )
    (net (code "40") (name "/Key2") (class "Default")
      (node (ref "K2") (pin "2") (pintype "passive"))
      (node (ref "U4") (pin "65") (pinfunction "PTA13_65") (pintype "passive"))
    )
    (net (code "41") (name "/Key3") (class "Default")
      (node (ref "K2") (pin "3") (pintype "passive"))
      (node (ref "U4") (pin "66") (pinfunction "PTA14_66") (pintype "passive"))
    )
    (net (code "42") (name "/Key4") (class "Default")
      (node (ref "K2") (pin "4") (pintype "passive"))
      (node (ref "U4") (pin "67") (pinfunction "PTA15_67") (pintype "passive"))
    )
    (net (code "43") (name "/Key5") (class "Default")
      (node (ref "K2") (pin "5") (pintype "passive"))
      (node (ref "U4") (pin "68") (pinfunction "PTA16_68") (pintype "passive"))
    )
    (net (code "44") (name "/LED_B") (class "Default")
      (node (ref "R15") (pin "1") (pinfunction "1_1") (pintype "passive"))
      (node (ref "U4") (pin "82") (pinfunction "PTB1_82") (pintype "passive"))
    )
    (net (code "45") (name "/LED_G") (class "Default")
      (node (ref "R14") (pin "1") (pinfunction "1_1") (pintype "passive"))
      (node (ref "U4") (pin "83") (pinfunction "PTB2_83") (pintype "passive"))
    )
    (net (code "46") (name "/LED_R") (class "Default")
      (node (ref "R13") (pin "1") (pinfunction "1_1") (pintype "passive"))
      (node (ref "U4") (pin "84") (pinfunction "PTB3_84") (pintype "passive"))
    )
    (net (code "47") (name "/L_RX") (class "Default")
      (node (ref "P5") (pin "2") (pinfunction "2_2") (pintype "passive"))
      (node (ref "P6") (pin "1") (pinfunction "1_1") (pintype "passive"))
      (node (ref "U4") (pin "2") (pinfunction "PTE1_2") (pintype "passive"))
    )
    (net (code "48") (name "/L_SDA") (class "Default")
      (node (ref "P5") (pin "1") (pinfunction "1_1") (pintype "passive"))
      (node (ref "P6") (pin "2") (pinfunction "2_2") (pintype "passive"))
      (node (ref "U4") (pin "1") (pinfunction "PTE0_1") (pintype "passive"))
    )
    (net (code "49") (name "/OL_DC") (class "Default")
      (node (ref "OLED1") (pin "6") (pinfunction "DC_6") (pintype "passive"))
      (node (ref "U4") (pin "125") (pinfunction "PTC18_125") (pintype "passive"))
    )
    (net (code "50") (name "/OL_RST") (class "Default")
      (node (ref "OLED1") (pin "5") (pinfunction "RST_5") (pintype "passive"))
      (node (ref "U4") (pin "126") (pinfunction "PTC19_126") (pintype "passive"))
    )
    (net (code "51") (name "/OL_SCL") (class "Default")
      (node (ref "OLED1") (pin "3") (pinfunction "SCL_3") (pintype "passive"))
      (node (ref "U4") (pin "128") (pinfunction "PTD1_128") (pintype "passive"))
    )
    (net (code "52") (name "/OL_SDA") (class "Default")
      (node (ref "OLED1") (pin "4") (pinfunction "SDA_4") (pintype "passive"))
      (node (ref "U4") (pin "127") (pinfunction "PTD0_127") (pintype "passive"))
    )
    (net (code "53") (name "/P0") (class "Default")
      (node (ref "P11") (pin "16") (pinfunction "16_16") (pintype "passive"))
      (node (ref "U4") (pin "54") (pinfunction "PTA4/EZP_CS_54") (pintype "passive"))
    )
    (net (code "54") (name "/P1") (class "Default")
      (node (ref "P11") (pin "15") (pinfunction "15_15") (pintype "passive"))
      (node (ref "U4") (pin "55") (pinfunction "PTA5_55") (pintype "passive"))
    )
    (net (code "55") (name "/P2") (class "Default")
      (node (ref "P11") (pin "14") (pinfunction "14_14") (pintype "passive"))
      (node (ref "U4") (pin "58") (pinfunction "PTA6_58") (pintype "passive"))
    )
    (net (code "56") (name "/P3") (class "Default")
      (node (ref "P11") (pin "13") (pinfunction "13_13") (pintype "passive"))
      (node (ref "U4") (pin "59") (pinfunction "PTA7_59") (pintype "passive"))
    )
    (net (code "57") (name "/P4") (class "Default")
      (node (ref "P11") (pin "12") (pinfunction "12_12") (pintype "passive"))
      (node (ref "U4") (pin "60") (pinfunction "PTA8_60") (pintype "passive"))
    )
    (net (code "58") (name "/P5") (class "Default")
      (node (ref "P11") (pin "11") (pinfunction "11_11") (pintype "passive"))
      (node (ref "U4") (pin "61") (pinfunction "PTA9_61") (pintype "passive"))
    )
    (net (code "59") (name "/P6") (class "Default")
      (node (ref "P11") (pin "10") (pinfunction "10_10") (pintype "passive"))
      (node (ref "U4") (pin "62") (pinfunction "PTA10_62") (pintype "passive"))
    )
    (net (code "60") (name "/P7") (class "Default")
      (node (ref "P11") (pin "9") (pinfunction "9_9") (pintype "passive"))
      (node (ref "U4") (pin "63") (pinfunction "PTA11_63") (pintype "passive"))
    )
    (net (code "61") (name "/PCLK") (class "Default")
      (node (ref "P11") (pin "6") (pinfunction "6_6") (pintype "passive"))
      (node (ref "R10") (pin "1") (pinfunction "1_1") (pintype "passive"))
      (node (ref "U4") (pin "47") (pinfunction "PTE26_47") (pintype "passive"))
    )
    (net (code "62") (name "/PGA0_DM") (class "Default")
      (node (ref "U4") (pin "28") (pinfunction "PGA0_DM/ADC0_DM0/ADC1_DM3_28") (pintype "passive"))
    )
    (net (code "63") (name "/PGA0_DP") (class "Default")
      (node (ref "U4") (pin "27") (pinfunction "PGA0_DP/ADC0_DP0/ADC1_DP3_27") (pintype "passive"))
    )
    (net (code "64") (name "/PGA1_DM") (class "Default")
      (node (ref "U4") (pin "30") (pinfunction "PGA1_DM/ADC1_DM0/ADC0_DM3_30") (pintype "passive"))
    )
    (net (code "65") (name "/PGA1_DP") (class "Default")
      (node (ref "U4") (pin "29") (pinfunction "PGA1_DP/ADC1_DP0/ADC0_DP3_29") (pintype "passive"))
    )
    (net (code "66") (name "/PTA1") (class "Default")
      (node (ref "U4") (pin "51") (pinfunction "PTA1/TDI_51") (pintype "passive"))
    )
    (net (code "67") (name "/PTA2") (class "Default")
      (node (ref "U4") (pin "52") (pinfunction "PTA2/TDO_52") (pintype "passive"))
    )
    (net (code "68") (name "/PTA17") (class "Default")
      (node (ref "U4") (pin "69") (pinfunction "PTA17_69") (pintype "passive"))
    )
    (net (code "69") (name "/PTA19") (class "Default")
      (node (ref "U4") (pin "73") (pinfunction "PTA19_73") (pintype "passive"))
    )
    (net (code "70") (name "/PTA24") (class "Default")
      (node (ref "U4") (pin "75") (pinfunction "PTA24_75") (pintype "passive"))
    )
    (net (code "71") (name "/PTA25") (class "Default")
      (node (ref "U4") (pin "76") (pinfunction "PTA25_76") (pintype "passive"))
    )
    (net (code "72") (name "/PTA26") (class "Default")
      (node (ref "R37") (pin "2") (pinfunction "2_2") (pintype "passive"))
      (node (ref "U4") (pin "77") (pinfunction "PTA26_77") (pintype "passive"))
    )
    (net (code "73") (name "/PTA27") (class "Default")
      (node (ref "R30") (pin "2") (pinfunction "2_2") (pintype "passive"))
      (node (ref "U4") (pin "78") (pinfunction "PTA27_78") (pintype "passive"))
    )
    (net (code "74") (name "/PTA28") (class "Default")
      (node (ref "R25") (pin "2") (pinfunction "2_2") (pintype "passive"))
      (node (ref "U4") (pin "79") (pinfunction "PTA28_79") (pintype "passive"))
    )
    (net (code "75") (name "/PTA29") (class "Default")
      (node (ref "R20") (pin "2") (pinfunction "2_2") (pintype "passive"))
      (node (ref "U4") (pin "80") (pinfunction "PTA29_80") (pintype "passive"))
    )
    (net (code "76") (name "/PTB0") (class "Default")
      (node (ref "P4") (pin "1") (pinfunction "IN_1") (pintype "passive"))
      (node (ref "U4") (pin "81") (pinfunction "PTB0_81") (pintype "passive"))
    )
    (net (code "77") (name "/PTB18") (class "Default")
      (node (ref "U4") (pin "97") (pinfunction "PTB18_97") (pintype "passive"))
    )
    (net (code "78") (name "/PTB19") (class "Default")
      (node (ref "U4") (pin "98") (pinfunction "PTB19_98") (pintype "passive"))
    )
    (net (code "79") (name "/PTC2") (class "Default")
      (node (ref "P3") (pin "1") (pinfunction "1_1") (pintype "passive"))
      (node (ref "U4") (pin "105") (pinfunction "PTC2_105") (pintype "passive"))
    )
    (net (code "80") (name "/PTC3") (class "Default")
      (node (ref "P3") (pin "2") (pinfunction "2_2") (pintype "passive"))
      (node (ref "U4") (pin "106") (pinfunction "PTC3_106") (pintype "passive"))
    )
    (net (code "81") (name "/PTC6") (class "Default")
      (node (ref "P7") (pin "1") (pinfunction "1_1") (pintype "passive"))
      (node (ref "U4") (pin "111") (pinfunction "PTC6_111") (pintype "passive"))
    )
    (net (code "82") (name "/PTC7") (class "Default")
      (node (ref "P7") (pin "2") (pinfunction "2_2") (pintype "passive"))
      (node (ref "U4") (pin "112") (pinfunction "PTC7_112") (pintype "passive"))
    )
    (net (code "83") (name "/PTC8") (class "Default")
      (node (ref "P7") (pin "3") (pinfunction "3_3") (pintype "passive"))
      (node (ref "U4") (pin "113") (pinfunction "PTC8_113") (pintype "passive"))
    )
    (net (code "84") (name "/PTC9") (class "Default")
      (node (ref "P7") (pin "4") (pinfunction "4_4") (pintype "passive"))
      (node (ref "U4") (pin "114") (pinfunction "PTC9_114") (pintype "passive"))
    )
    (net (code "85") (name "/PTC10") (class "Default")
      (node (ref "P7") (pin "5") (pinfunction "5_5") (pintype "passive"))
      (node (ref "U4") (pin "115") (pinfunction "PTC10_115") (pintype "passive"))
    )
    (net (code "86") (name "/PTC11") (class "Default")
      (node (ref "P7") (pin "6") (pinfunction "6_6") (pintype "passive"))
      (node (ref "U4") (pin "116") (pinfunction "PTC11_116") (pintype "passive"))
    )
    (net (code "87") (name "/PTC12") (class "Default")
      (node (ref "P7") (pin "7") (pinfunction "7_7") (pintype "passive"))
      (node (ref "U4") (pin "117") (pinfunction "PTC12_117") (pintype "passive"))
    )
    (net (code "88") (name "/PTC13") (class "Default")
      (node (ref "P7") (pin "8") (pinfunction "8_8") (pintype "passive"))
      (node (ref "U4") (pin "118") (pinfunction "PTC13_118") (pintype "passive"))
    )
    (net (code "89") (name "/PTC14") (class "Default")
      (node (ref "P7") (pin "9") (pinfunction "9_9") (pintype "passive"))
      (node (ref "U4") (pin "119") (pinfunction "PTC14_119") (pintype "passive"))
    )
    (net (code "90") (name "/PTC15") (class "Default")
      (node (ref "P7") (pin "10") (pinfunction "10_10") (pintype "passive"))
      (node (ref "U4") (pin "120") (pinfunction "PTC15_120") (pintype "passive"))
    )
    (net (code "91") (name "/PTC16") (class "Default")
      (node (ref "U4") (pin "123") (pinfunction "PTC16_123") (pintype "passive"))
    )
    (net (code "92") (name "/PTC17") (class "Default")
      (node (ref "U4") (pin "124") (pinfunction "PTC17_124") (pintype "passive"))
    )
    (net (code "93") (name "/PTD2") (class "Default")
      (node (ref "U4") (pin "129") (pinfunction "PTD2_129") (pintype "passive"))
    )
    (net (code "94") (name "/PTD3") (class "Default")
      (node (ref "P9") (pin "7") (pinfunction "7_7") (pintype "passive"))
      (node (ref "U4") (pin "130") (pinfunction "PTD3_130") (pintype "passive"))
    )
    (net (code "95") (name "/PTD4") (class "Default")
      (node (ref "P9") (pin "6") (pinfunction "6_6") (pintype "passive"))
      (node (ref "U4") (pin "131") (pinfunction "PTD4_131") (pintype "passive"))
    )
    (net (code "96") (name "/PTD5") (class "Default")
      (node (ref "P9") (pin "5") (pinfunction "5_5") (pintype "passive"))
      (node (ref "U4") (pin "132") (pinfunction "PTD5_132") (pintype "passive"))
    )
    (net (code "97") (name "/PTD6") (class "Default")
      (node (ref "P9") (pin "4") (pinfunction "4_4") (pintype "passive"))
      (node (ref "U4") (pin "133") (pinfunction "PTD6_133") (pintype "passive"))
    )
    (net (code "98") (name "/PTD7") (class "Default")
      (node (ref "U4") (pin "136") (pinfunction "PTD7_136") (pintype "passive"))
    )
    (net (code "99") (name "/PTD8") (class "Default")
      (node (ref "U4") (pin "137") (pinfunction "PTD8_137") (pintype "passive"))
    )
    (net (code "100") (name "/PTD9") (class "Default")
      (node (ref "U4") (pin "138") (pinfunction "PTD9_138") (pintype "passive"))
    )
    (net (code "101") (name "/PTD10") (class "Default")
      (node (ref "U4") (pin "139") (pinfunction "PTD10_139") (pintype "passive"))
    )
    (net (code "102") (name "/PTD11") (class "Default")
      (node (ref "U4") (pin "140") (pinfunction "PTD11_140") (pintype "passive"))
    )
    (net (code "103") (name "/PTD12") (class "Default")
      (node (ref "U4") (pin "141") (pinfunction "PTD12_141") (pintype "passive"))
    )
    (net (code "104") (name "/PTD13") (class "Default")
      (node (ref "U4") (pin "142") (pinfunction "PTD13_142") (pintype "passive"))
    )
    (net (code "105") (name "/PTD14") (class "Default")
      (node (ref "U4") (pin "143") (pinfunction "PTD14_143") (pintype "passive"))
    )
    (net (code "106") (name "/PTD15") (class "Default")
      (node (ref "U4") (pin "144") (pinfunction "PTD15_144") (pintype "passive"))
    )
    (net (code "107") (name "/PTE2") (class "Default")
      (node (ref "U4") (pin "3") (pinfunction "PTE2_3") (pintype "passive"))
    )
    (net (code "108") (name "/PTE3") (class "Default")
      (node (ref "U4") (pin "4") (pinfunction "PTE3_4") (pintype "passive"))
    )
    (net (code "109") (name "/PTE4") (class "Default")
      (node (ref "U4") (pin "7") (pinfunction "PTE4_7") (pintype "passive"))
    )
    (net (code "110") (name "/PTE5") (class "Default")
      (node (ref "U4") (pin "8") (pinfunction "PTE5_8") (pintype "passive"))
    )
    (net (code "111") (name "/PTE6") (class "Default")
      (node (ref "U4") (pin "9") (pinfunction "PTE6_9") (pintype "passive"))
    )
    (net (code "112") (name "/PTE7") (class "Default")
      (node (ref "U4") (pin "10") (pinfunction "PTE7_10") (pintype "passive"))
    )
    (net (code "113") (name "/PTE8") (class "Default")
      (node (ref "U4") (pin "11") (pinfunction "PTE8_11") (pintype "passive"))
    )
    (net (code "114") (name "/PTE9") (class "Default")
      (node (ref "U4") (pin "12") (pinfunction "PTE9_12") (pintype "passive"))
    )
    (net (code "115") (name "/PTE10") (class "Default")
      (node (ref "U4") (pin "13") (pinfunction "PTE10_13") (pintype "passive"))
    )
    (net (code "116") (name "/PTE11") (class "Default")
      (node (ref "U4") (pin "14") (pinfunction "PTE11_14") (pintype "passive"))
    )
    (net (code "117") (name "/PTE12") (class "Default")
      (node (ref "U4") (pin "15") (pinfunction "PTE12_15") (pintype "passive"))
    )
    (net (code "118") (name "/PTE24") (class "Default")
      (node (ref "P11") (pin "3") (pinfunction "3_3") (pintype "passive"))
      (node (ref "R9") (pin "2") (pinfunction "2_2") (pintype "passive"))
      (node (ref "U4") (pin "45") (pinfunction "PTE24_45") (pintype "passive"))
    )
    (net (code "119") (name "/RESET_B") (class "Default")
      (node (ref "C39") (pin "2") (pinfunction "2_2") (pintype "passive"))
      (node (ref "K5") (pin "1") (pinfunction "1_1") (pintype "passive"))
      (node (ref "R45") (pin "1") (pinfunction "1_1") (pintype "passive"))
      (node (ref "U4") (pin "74") (pinfunction "RESET_B_74") (pintype "passive"))
    )
    (net (code "120") (name "/Rc_1") (class "Default")
      (node (ref "P10") (pin "4") (pinfunction "4_4") (pintype "passive"))
      (node (ref "R17") (pin "1") (pinfunction "1_1") (pintype "passive"))
    )
    (net (code "121") (name "/Rc_2") (class "Default")
      (node (ref "P10") (pin "3") (pinfunction "3_3") (pintype "passive"))
      (node (ref "R22") (pin "1") (pinfunction "1_1") (pintype "passive"))
    )
    (net (code "122") (name "/Rc_3") (class "Default")
      (node (ref "P10") (pin "2") (pinfunction "2_2") (pintype "passive"))
      (node (ref "R26") (pin "1") (pinfunction "1_1") (pintype "passive"))
    )
    (net (code "123") (name "/Rc_4") (class "Default")
      (node (ref "P10") (pin "1") (pinfunction "1_1") (pintype "passive"))
      (node (ref "R33") (pin "1") (pinfunction "1_1") (pintype "passive"))
    )
    (net (code "124") (name "/SWD_CLK") (class "Default")
      (node (ref "SWD1") (pin "4") (pinfunction "CLK_4") (pintype "passive"))
      (node (ref "U4") (pin "50") (pinfunction "PTA0/TCK/SWD_CLK_50") (pintype "passive"))
    )
    (net (code "125") (name "/SWD_DIO") (class "Default")
      (node (ref "SWD1") (pin "3") (pinfunction "DIO_3") (pintype "passive"))
      (node (ref "U4") (pin "53") (pinfunction "PTA3/TMS/SWD_DIO_53") (pintype "passive"))
    )
    (net (code "126") (name "/VDDA") (class "Default")
      (node (ref "C1") (pin "2") (pinfunction "2_2") (pintype "passive"))
      (node (ref "C2") (pin "2") (pinfunction "2_2") (pintype "passive"))
      (node (ref "FB1") (pin "1") (pinfunction "1_1") (pintype "passive"))
      (node (ref "U4") (pin "31") (pinfunction "VDDA_31") (pintype "passive"))
      (node (ref "U4") (pin "32") (pinfunction "VREFH_32") (pintype "passive"))
    )
    (net (code "127") (name "/VREFL") (class "Default")
      (node (ref "C1") (pin "1") (pinfunction "1_1") (pintype "passive"))
      (node (ref "C2") (pin "1") (pinfunction "1_1") (pintype "passive"))
      (node (ref "FB2") (pin "1") (pinfunction "1_1") (pintype "passive"))
      (node (ref "U4") (pin "33") (pinfunction "VREFL_33") (pintype "passive"))
      (node (ref "U4") (pin "34") (pinfunction "VSSA_34") (pintype "passive"))
    )
    (net (code "128") (name "/XTAL") (class "Default")
      (node (ref "U4") (pin "40") (pinfunction "XTAL_40") (pintype "passive"))
    )
    (net (code "129") (name "AGND") (class "Default")
      (node (ref "C10") (pin "1") (pinfunction "1_1") (pintype "passive"))
      (node (ref "C11") (pin "2") (pinfunction "2_2") (pintype "passive"))
      (node (ref "C12") (pin "1") (pinfunction "1_1") (pintype "passive"))
      (node (ref "C13") (pin "2") (pinfunction "2_2") (pintype "passive"))
      (node (ref "C14") (pin "1") (pinfunction "1_1") (pintype "passive"))
      (node (ref "C15") (pin "2") (pinfunction "2_2") (pintype "passive"))
      (node (ref "C16") (pin "1") (pinfunction "1_1") (pintype "passive"))
      (node (ref "C17") (pin "2") (pinfunction "2_2") (pintype "passive"))
      (node (ref "C19") (pin "2") (pinfunction "2_2") (pintype "passive"))
      (node (ref "C20") (pin "1") (pinfunction "1_1") (pintype "passive"))
      (node (ref "C21") (pin "2") (pinfunction "2_2") (pintype "passive"))
      (node (ref "C22") (pin "1") (pinfunction "1_1") (pintype "passive"))
      (node (ref "C23") (pin "1") (pinfunction "1_1") (pintype "passive"))
      (node (ref "C24") (pin "2") (pinfunction "2_2") (pintype "passive"))
      (node (ref "C27") (pin "1") (pinfunction "1_1") (pintype "passive"))
      (node (ref "C28") (pin "1") (pinfunction "1_1") (pintype "passive"))
      (node (ref "C29") (pin "1") (pinfunction "1_1") (pintype "passive"))
      (node (ref "C3") (pin "2") (pinfunction "2_2") (pintype "passive"))
      (node (ref "C30") (pin "1") (pinfunction "1_1") (pintype "passive"))
      (node (ref "C31") (pin "1") (pinfunction "1_1") (pintype "passive"))
      (node (ref "C32") (pin "1") (pinfunction "1_1") (pintype "passive"))
      (node (ref "C33") (pin "1") (pinfunction "1_1") (pintype "passive"))
      (node (ref "C34") (pin "1") (pinfunction "1_1") (pintype "passive"))
      (node (ref "C35") (pin "1") (pinfunction "1_1") (pintype "passive"))
      (node (ref "C36") (pin "1") (pinfunction "1_1") (pintype "passive"))
      (node (ref "C37") (pin "2") (pinfunction "2_2") (pintype "passive"))
      (node (ref "C38") (pin "2") (pinfunction "2_2") (pintype "passive"))
      (node (ref "C39") (pin "1") (pinfunction "1_1") (pintype "passive"))
      (node (ref "C4") (pin "1") (pinfunction "1_1") (pintype "passive"))
      (node (ref "C5") (pin "2") (pinfunction "2_2") (pintype "passive"))
      (node (ref "C6") (pin "1") (pinfunction "1_1") (pintype "passive"))
      (node (ref "C7") (pin "2") (pinfunction "2_2") (pintype "passive"))
      (node (ref "C8") (pin "1") (pinfunction "1_1") (pintype "passive"))
      (node (ref "C9") (pin "2") (pinfunction "2_2") (pintype "passive"))
      (node (ref "FB2") (pin "2") (pinfunction "2_2") (pintype "passive"))
      (node (ref "K5") (pin "2") (pinfunction "2_2") (pintype "passive"))
      (node (ref "OLED1") (pin "1") (pinfunction "AGND_1") (pintype "passive"))
      (node (ref "P9") (pin "1") (pinfunction "1_1") (pintype "passive"))
      (node (ref "P9") (pin "3") (pinfunction "3_3") (pintype "passive"))
      (node (ref "PNP1") (pin "1") (pinfunction "C_1") (pintype "passive"))
      (node (ref "R21") (pin "1") (pinfunction "1_1") (pintype "passive"))
      (node (ref "R43") (pin "2") (pinfunction "2_2") (pintype "passive"))
      (node (ref "R46") (pin "1") (pinfunction "1_1") (pintype "passive"))
      (node (ref "R47") (pin "1") (pinfunction "1_1") (pintype "passive"))
      (node (ref "SWD1") (pin "2") (pinfunction "GND_2") (pintype "passive"))
      (node (ref "U1") (pin "1") (pinfunction "GND_1") (pintype "power_in"))
      (node (ref "U1") (pin "2") (pinfunction "~{EN}_2") (pintype "power_in"))
      (node (ref "U2") (pin "1") (pinfunction "GND_1") (pintype "power_in"))
      (node (ref "U2") (pin "2") (pinfunction "~{EN}_2") (pintype "power_in"))
      (node (ref "U3") (pin "1") (pinfunction "GND_1") (pintype "power_in"))
      (node (ref "U3") (pin "2") (pinfunction "~{EN}_2") (pintype "power_in"))
      (node (ref "U4") (pin "107") (pinfunction "VSS_107") (pintype "passive"))
      (node (ref "U4") (pin "121") (pinfunction "VSS_121") (pintype "passive"))
      (node (ref "U4") (pin "134") (pinfunction "VSS_134") (pintype "passive"))
      (node (ref "U4") (pin "17") (pinfunction "VSS_17") (pintype "passive"))
      (node (ref "U4") (pin "18") (pinfunction "VSS_18") (pintype "passive"))
      (node (ref "U4") (pin "44") (pinfunction "VSS_44") (pintype "passive"))
      (node (ref "U4") (pin "57") (pinfunction "VSS_57") (pintype "passive"))
      (node (ref "U4") (pin "6") (pinfunction "VSS_6") (pintype "passive"))
      (node (ref "U4") (pin "71") (pinfunction "VSS_71") (pintype "passive"))
      (node (ref "U4") (pin "93") (pinfunction "VSS_93") (pintype "passive"))
      (node (ref "U5") (pin "1") (pinfunction "GND_1") (pintype "power_in"))
      (node (ref "U5") (pin "2") (pinfunction "~{EN}_2") (pintype "power_in"))
      (node (ref "U6") (pin "2") (pinfunction "ON_2") (pintype "passive"))
      (node (ref "U6") (pin "3") (pinfunction "GND_3") (pintype "passive"))
      (node (ref "XTAL1") (pin "2") (pinfunction "AGND_2") (pintype "passive"))
      (node (ref "Z1") (pin "1") (pinfunction "A_1") (pintype "passive"))
      (node (ref "Z2") (pin "1") (pinfunction "A_1") (pintype "passive"))
    )
    (net (code "130") (name "GND") (class "Default")
      (node (ref "C25") (pin "2") (pinfunction "2_2") (pintype "passive"))
      (node (ref "C26") (pin "2") (pinfunction "2_2") (pintype "passive"))
      (node (ref "LED6") (pin "2") (pinfunction "K_2") (pintype "passive"))
      (node (ref "LED7") (pin "2") (pinfunction "K_2") (pintype "passive"))
      (node (ref "P12") (pin "2") (pinfunction "2_2") (pintype "passive"))
      (node (ref "P12") (pin "4") (pinfunction "4_4") (pintype "passive"))
      (node (ref "P12") (pin "6") (pinfunction "6_6") (pintype "passive"))
      (node (ref "P12") (pin "8") (pinfunction "8_8") (pintype "passive"))
      (node (ref "P13") (pin "2") (pinfunction "2_2") (pintype "passive"))
      (node (ref "R19") (pin "2") (pinfunction "2_2") (pintype "passive"))
      (node (ref "R24") (pin "2") (pinfunction "2_2") (pintype "passive"))
      (node (ref "R28") (pin "2") (pinfunction "2_2") (pintype "passive"))
      (node (ref "R29") (pin "2") (pinfunction "2_2") (pintype "passive"))
      (node (ref "R31") (pin "2") (pinfunction "2_2") (pintype "passive"))
      (node (ref "R32") (pin "2") (pinfunction "2_2") (pintype "passive"))
      (node (ref "R35") (pin "2") (pinfunction "2_2") (pintype "passive"))
      (node (ref "R36") (pin "2") (pinfunction "2_2") (pintype "passive"))
      (node (ref "R42") (pin "1") (pinfunction "1_1") (pintype "passive"))
      (node (ref "R43") (pin "1") (pinfunction "1_1") (pintype "passive"))
      (node (ref "R47") (pin "2") (pinfunction "2_2") (pintype "passive"))
      (node (ref "T1") (pin "2") (pinfunction "GND_2") (pintype "passive"))
      (node (ref "T2") (pin "2") (pinfunction "M2_2") (pintype "passive"))
    )
    (net (code "131") (name "MCU-3V3") (class "Default")
      (node (ref "1") (pin "1") (pinfunction "K_1") (pintype "passive"))
      (node (ref "C17") (pin "1") (pinfunction "1_1") (pintype "passive"))
      (node (ref "C28") (pin "2") (pinfunction "2_2") (pintype "passive"))
      (node (ref "C29") (pin "2") (pinfunction "2_2") (pintype "passive"))
      (node (ref "C30") (pin "2") (pinfunction "2_2") (pintype "passive"))
      (node (ref "C31") (pin "2") (pinfunction "2_2") (pintype "passive"))
      (node (ref "C32") (pin "2") (pinfunction "2_2") (pintype "passive"))
      (node (ref "C33") (pin "2") (pinfunction "2_2") (pintype "passive"))
      (node (ref "C34") (pin "2") (pinfunction "2_2") (pintype "passive"))
      (node (ref "C35") (pin "2") (pinfunction "2_2") (pintype "passive"))
      (node (ref "C36") (pin "2") (pinfunction "2_2") (pintype "passive"))
      (node (ref "C37") (pin "1") (pinfunction "1_1") (pintype "passive"))
      (node (ref "C38") (pin "1") (pinfunction "1_1") (pintype "passive"))
      (node (ref "C5") (pin "1") (pinfunction "1_1") (pintype "passive"))
      (node (ref "C6") (pin "2") (pinfunction "2_2") (pintype "passive"))
      (node (ref "F1") (pin "1") (pinfunction "1_1") (pintype "passive"))
      (node (ref "FB1") (pin "2") (pinfunction "2_2") (pintype "passive"))
      (node (ref "R45") (pin "2") (pinfunction "2_2") (pintype "passive"))
      (node (ref "SWD1") (pin "1") (pinfunction "VCC_1") (pintype "passive"))
      (node (ref "U4") (pin "108") (pinfunction "VDD_108") (pintype "passive"))
      (node (ref "U4") (pin "122") (pinfunction "VDD_122") (pintype "passive"))
      (node (ref "U4") (pin "135") (pinfunction "VDD_135") (pintype "passive"))
      (node (ref "U4") (pin "16") (pinfunction "VDD_16") (pintype "passive"))
      (node (ref "U4") (pin "21") (pinfunction "VOUT33_21") (pintype "passive"))
      (node (ref "U4") (pin "43") (pinfunction "VDD_43") (pintype "passive"))
      (node (ref "U4") (pin "5") (pinfunction "VDD_5") (pintype "passive"))
      (node (ref "U4") (pin "56") (pinfunction "VDD_56") (pintype "passive"))
      (node (ref "U4") (pin "70") (pinfunction "VDD_70") (pintype "passive"))
      (node (ref "U4") (pin "94") (pinfunction "VDD_94") (pintype "passive"))
      (node (ref "XTAL1") (pin "1") (pinfunction "EN_1") (pintype "passive"))
      (node (ref "XTAL1") (pin "4") (pinfunction "VCC_4") (pintype "power_in"))
      (node (ref "Z1") (pin "2") (pinfunction "K_2") (pintype "passive"))
      (node (ref "Z2") (pin "2") (pinfunction "K_2") (pintype "passive"))
    )
    (net (code "132") (name "MCU_3V3") (class "Default")
      (node (ref "C11") (pin "1") (pinfunction "1_1") (pintype "passive"))
      (node (ref "C12") (pin "2") (pinfunction "2_2") (pintype "passive"))
      (node (ref "F1") (pin "2") (pinfunction "2_2") (pintype "passive"))
      (node (ref "LED1") (pin "4") (pinfunction "K4_4") (pintype "passive"))
      (node (ref "OLED1") (pin "2") (pinfunction "VCC3.3_2") (pintype "passive"))
      (node (ref "P12") (pin "1") (pinfunction "1_1") (pintype "passive"))
      (node (ref "P12") (pin "3") (pinfunction "3_3") (pintype "passive"))
      (node (ref "P5") (pin "4") (pinfunction "4_4") (pintype "passive"))
      (node (ref "P9") (pin "2") (pinfunction "2_2") (pintype "passive"))
      (node (ref "R11") (pin "1") (pinfunction "1_1") (pintype "passive"))
      (node (ref "R12") (pin "2") (pinfunction "2_2") (pintype "passive"))
      (node (ref "R3") (pin "1") (pinfunction "1_1") (pintype "passive"))
      (node (ref "R4") (pin "1") (pinfunction "1_1") (pintype "passive"))
      (node (ref "R5") (pin "1") (pinfunction "1_1") (pintype "passive"))
      (node (ref "R6") (pin "1") (pinfunction "1_1") (pintype "passive"))
      (node (ref "R7") (pin "1") (pinfunction "1_1") (pintype "passive"))
      (node (ref "R8") (pin "1") (pinfunction "1_1") (pintype "passive"))
      (node (ref "U2") (pin "5") (pinfunction "OUT_5") (pintype "power_in"))
      (node (ref "U2") (pin "6") (pinfunction "OUT_6") (pintype "power_in"))
      (node (ref "U2") (pin "7") (pinfunction "FB_7") (pintype "power_in"))
    )
    (net (code "133") (name "Net-(1-A)") (class "Default")
      (node (ref "1") (pin "2") (pinfunction "A_2") (pintype "passive"))
      (node (ref "R46") (pin "2") (pinfunction "2_2") (pintype "passive"))
    )
    (net (code "134") (name "Net-(K3-com)") (class "Default")
      (node (ref "K3") (pin "2") (pinfunction "com_2") (pintype "passive"))
      (node (ref "R38") (pin "2") (pinfunction "2_2") (pintype "passive"))
      (node (ref "T2") (pin "1") (pinfunction "M1_1") (pintype "passive"))
    )
    (net (code "135") (name "Net-(K4-ON-Pad3)") (class "Default")
      (node (ref "K4") (pin "3") (pinfunction "ON_3") (pintype "passive"))
      (node (ref "R39") (pin "2") (pinfunction "2_2") (pintype "passive"))
    )
    (net (code "136") (name "Net-(LED1-K1)") (class "Default")
      (node (ref "LED1") (pin "1") (pinfunction "K1_1") (pintype "passive"))
      (node (ref "R13") (pin "2") (pinfunction "2_2") (pintype "passive"))
    )
    (net (code "137") (name "Net-(LED1-K2)") (class "Default")
      (node (ref "LED1") (pin "2") (pinfunction "K2_2") (pintype "passive"))
      (node (ref "R14") (pin "2") (pinfunction "2_2") (pintype "passive"))
    )
    (net (code "138") (name "Net-(LED1-K3)") (class "Default")
      (node (ref "LED1") (pin "3") (pinfunction "K3_3") (pintype "passive"))
      (node (ref "R15") (pin "2") (pinfunction "2_2") (pintype "passive"))
    )
    (net (code "139") (name "Net-(LED2-K)") (class "Default")
      (node (ref "LED2") (pin "2") (pinfunction "K_2") (pintype "passive"))
      (node (ref "R29") (pin "1") (pinfunction "1_1") (pintype "passive"))
    )
    (net (code "140") (name "Net-(LED3-K)") (class "Default")
      (node (ref "LED3") (pin "2") (pinfunction "K_2") (pintype "passive"))
      (node (ref "R31") (pin "1") (pinfunction "1_1") (pintype "passive"))
    )
    (net (code "141") (name "Net-(LED4-K)") (class "Default")
      (node (ref "LED4") (pin "2") (pinfunction "K_2") (pintype "passive"))
      (node (ref "R32") (pin "1") (pinfunction "1_1") (pintype "passive"))
    )
    (net (code "142") (name "Net-(LED5-K)") (class "Default")
      (node (ref "LED5") (pin "2") (pinfunction "K_2") (pintype "passive"))
      (node (ref "R36") (pin "1") (pinfunction "1_1") (pintype "passive"))
    )
    (net (code "143") (name "Net-(LED6-A)") (class "Default")
      (node (ref "LED6") (pin "1") (pinfunction "A_1") (pintype "passive"))
      (node (ref "R40") (pin "1") (pinfunction "1_1") (pintype "passive"))
    )
    (net (code "144") (name "Net-(LED7-A)") (class "Default")
      (node (ref "LED7") (pin "1") (pinfunction "A_1") (pintype "passive"))
      (node (ref "R38") (pin "1") (pinfunction "1_1") (pintype "passive"))
    )
    (net (code "145") (name "Net-(PNP1-B)") (class "Default")
      (node (ref "PNP1") (pin "2") (pinfunction "B_2") (pintype "passive"))
      (node (ref "R2") (pin "1") (pinfunction "1_1") (pintype "passive"))
    )
    (net (code "146") (name "Net-(PNP1-E)") (class "Default")
      (node (ref "BUZZER1") (pin "2") (pinfunction "2_2") (pintype "output"))
      (node (ref "PNP1") (pin "3") (pinfunction "E_3") (pintype "passive"))
    )
    (net (code "147") (name "Net-(R17-Pad2)") (class "Default")
      (node (ref "R17") (pin "2") (pinfunction "2_2") (pintype "passive"))
      (node (ref "R18") (pin "1") (pinfunction "1_1") (pintype "passive"))
      (node (ref "R20") (pin "1") (pinfunction "1_1") (pintype "passive"))
    )
    (net (code "148") (name "Net-(R18-Pad2)") (class "Default")
      (node (ref "R18") (pin "2") (pinfunction "2_2") (pintype "passive"))
      (node (ref "R19") (pin "1") (pinfunction "1_1") (pintype "passive"))
    )
    (net (code "149") (name "Net-(R22-Pad2)") (class "Default")
      (node (ref "R22") (pin "2") (pinfunction "2_2") (pintype "passive"))
      (node (ref "R23") (pin "1") (pinfunction "1_1") (pintype "passive"))
      (node (ref "R25") (pin "1") (pinfunction "1_1") (pintype "passive"))
    )
    (net (code "150") (name "Net-(R23-Pad2)") (class "Default")
      (node (ref "R23") (pin "2") (pinfunction "2_2") (pintype "passive"))
      (node (ref "R24") (pin "1") (pinfunction "1_1") (pintype "passive"))
    )
    (net (code "151") (name "Net-(R26-Pad2)") (class "Default")
      (node (ref "R26") (pin "2") (pinfunction "2_2") (pintype "passive"))
      (node (ref "R27") (pin "1") (pinfunction "1_1") (pintype "passive"))
      (node (ref "R30") (pin "1") (pinfunction "1_1") (pintype "passive"))
    )
    (net (code "152") (name "Net-(R27-Pad2)") (class "Default")
      (node (ref "R27") (pin "2") (pinfunction "2_2") (pintype "passive"))
      (node (ref "R28") (pin "1") (pinfunction "1_1") (pintype "passive"))
    )
    (net (code "153") (name "Net-(R33-Pad2)") (class "Default")
      (node (ref "R33") (pin "2") (pinfunction "2_2") (pintype "passive"))
      (node (ref "R34") (pin "1") (pinfunction "1_1") (pintype "passive"))
      (node (ref "R37") (pin "1") (pinfunction "1_1") (pintype "passive"))
    )
    (net (code "154") (name "Net-(R34-Pad2)") (class "Default")
      (node (ref "R34") (pin "2") (pinfunction "2_2") (pintype "passive"))
      (node (ref "R35") (pin "1") (pinfunction "1_1") (pintype "passive"))
    )
    (net (code "155") (name "Net-(R39-Pad1)") (class "Default")
      (node (ref "R39") (pin "1") (pinfunction "1_1") (pintype "passive"))
      (node (ref "R41") (pin "2") (pinfunction "2_2") (pintype "passive"))
      (node (ref "R44") (pin "2") (pinfunction "2_2") (pintype "passive"))
    )
    (net (code "156") (name "Net-(T1-VCC)") (class "Default")
      (node (ref "K4") (pin "1") (pinfunction "ON_1") (pintype "passive"))
      (node (ref "T1") (pin "1") (pinfunction "VCC_1") (pintype "passive"))
    )
    (net (code "157") (name "Net-(U4-VREF_OUT{slash}ADC1_SE18)") (class "Default")
      (node (ref "C27") (pin "2") (pinfunction "2_2") (pintype "passive"))
      (node (ref "U4") (pin "37") (pinfunction "VREF_OUT/ADC1_SE18_37") (pintype "passive"))
    )
    (net (code "158") (name "Net-(U6-ADJ)") (class "Default")
      (node (ref "R16") (pin "1") (pinfunction "1_1") (pintype "passive"))
      (node (ref "R21") (pin "2") (pinfunction "2_2") (pintype "passive"))
      (node (ref "U6") (pin "1") (pinfunction "ADJ_1") (pintype "passive"))
    )
    (net (code "159") (name "unconnected-(K3-ON-Pad3)") (class "Default")
      (node (ref "K3") (pin "3") (pinfunction "ON_3") (pintype "passive"))
    )
    (net (code "160") (name "unconnected-(P11-Pad17)") (class "Default")
      (node (ref "P11") (pin "17") (pinfunction "17_17") (pintype "passive"))
    )
    (net (code "161") (name "unconnected-(P11-Pad18)") (class "Default")
      (node (ref "P11") (pin "18") (pinfunction "18_18") (pintype "passive"))
    )
    (net (code "162") (name "unconnected-(P11-Pad19)") (class "Default")
      (node (ref "P11") (pin "19") (pinfunction "19_19") (pintype "passive"))
    )
    (net (code "163") (name "unconnected-(P11-Pad20)") (class "Default")
      (node (ref "P11") (pin "20") (pinfunction "20_20") (pintype "passive"))
    )
    (net (code "164") (name "unconnected-(R2-Pad2)") (class "Default")
      (node (ref "R2") (pin "2") (pinfunction "2_2") (pintype "passive"))
    )
    (net (code "165") (name "unconnected-(R44-Pad1)") (class "Default")
      (node (ref "R44") (pin "1") (pinfunction "1_1") (pintype "passive"))
    )
    (net (code "166") (name "unconnected-(U1-~{RESET}-Pad8)") (class "Default")
      (node (ref "U1") (pin "8") (pinfunction "~{RESET}_8") (pintype "power_in"))
    )
    (net (code "167") (name "unconnected-(U2-~{RESET}-Pad8)") (class "Default")
      (node (ref "U2") (pin "8") (pinfunction "~{RESET}_8") (pintype "power_in"))
    )
    (net (code "168") (name "unconnected-(U3-~{RESET}-Pad8)") (class "Default")
      (node (ref "U3") (pin "8") (pinfunction "~{RESET}_8") (pintype "power_in"))
    )
    (net (code "169") (name "unconnected-(U4-USB0_DM-Pad20)") (class "Default")
      (node (ref "U4") (pin "20") (pinfunction "USB0_DM_20") (pintype "passive+no_connect"))
    )
    (net (code "170") (name "unconnected-(U4-USB0_DP-Pad19)") (class "Default")
      (node (ref "U4") (pin "19") (pinfunction "USB0_DP_19") (pintype "passive+no_connect"))
    )
    (net (code "171") (name "unconnected-(U4-VBAT-Pad42)") (class "Default")
      (node (ref "U4") (pin "42") (pinfunction "VBAT_42") (pintype "passive+no_connect"))
    )
    (net (code "172") (name "unconnected-(U4-VREGIN-Pad22)") (class "Default")
      (node (ref "U4") (pin "22") (pinfunction "VREGIN_22") (pintype "passive+no_connect"))
    )
    (net (code "173") (name "unconnected-(U5-~{RESET}-Pad8)") (class "Default")
      (node (ref "U5") (pin "8") (pinfunction "~{RESET}_8") (pintype "power_in"))
    )
  )
)
